# KEY_PLC1.net
KiCad netlist of a schematic drawn in Altium Designer
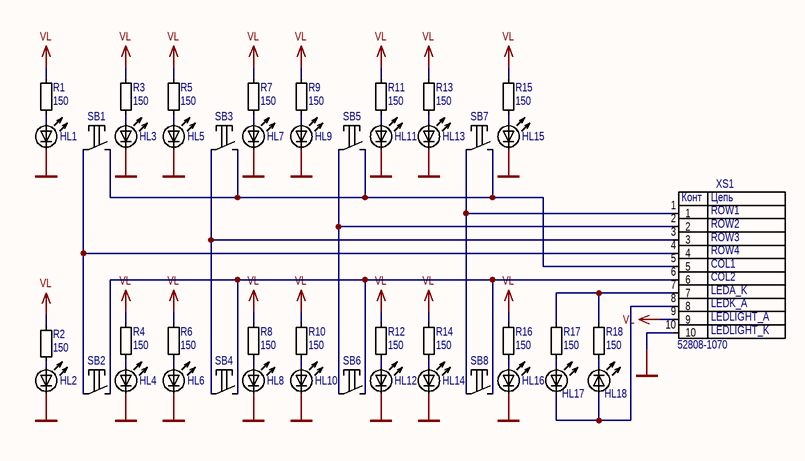
[diagram p0: KEY_PLC1.SchDoc]

(export (version "E")
  (design (tool "Eeschema 10.0.6"))
  (components
    (comp (ref "HL1")
      (value "BL-LS0805UYC")
      (footprint "LED_0805")
      (libsource (lib "KEY_PLC1") (part "BL-LS0805UYC"))
    )
    (comp (ref "HL2")
      (value "BL-LS0805UYC")
      (footprint "LED_0805")
      (libsource (lib "KEY_PLC1") (part "BL-LS0805UYC"))
    )
    (comp (ref "HL3")
      (value "BL-LS0805UYC")
      (footprint "LED_0805")
      (libsource (lib "KEY_PLC1") (part "BL-LS0805UYC"))
    )
    (comp (ref "HL4")
      (value "BL-LS0805UYC")
      (footprint "LED_0805")
      (libsource (lib "KEY_PLC1") (part "BL-LS0805UYC"))
    )
    (comp (ref "HL5")
      (value "BL-LS0805UYC")
      (footprint "LED_0805")
      (libsource (lib "KEY_PLC1") (part "BL-LS0805UYC"))
    )
    (comp (ref "HL6")
      (value "BL-LS0805UYC")
      (footprint "LED_0805")
      (libsource (lib "KEY_PLC1") (part "BL-LS0805UYC"))
    )
    (comp (ref "HL7")
      (value "BL-LS0805UYC")
      (footprint "LED_0805")
      (libsource (lib "KEY_PLC1") (part "BL-LS0805UYC"))
    )
    (comp (ref "HL8")
      (value "BL-LS0805UYC")
      (footprint "LED_0805")
      (libsource (lib "KEY_PLC1") (part "BL-LS0805UYC"))
    )
    (comp (ref "HL9")
      (value "BL-LS0805UYC")
      (footprint "LED_0805")
      (libsource (lib "KEY_PLC1") (part "BL-LS0805UYC"))
    )
    (comp (ref "HL10")
      (value "BL-LS0805UYC")
      (footprint "LED_0805")
      (libsource (lib "KEY_PLC1") (part "BL-LS0805UYC"))
    )
    (comp (ref "HL11")
      (value "BL-LS0805UYC")
      (footprint "LED_0805")
      (libsource (lib "KEY_PLC1") (part "BL-LS0805UYC"))
    )
    (comp (ref "HL12")
      (value "BL-LS0805UYC")
      (footprint "LED_0805")
      (libsource (lib "KEY_PLC1") (part "BL-LS0805UYC"))
    )
    (comp (ref "HL13")
      (value "BL-LS0805UYC")
      (footprint "LED_0805")
      (libsource (lib "KEY_PLC1") (part "BL-LS0805UYC"))
    )
    (comp (ref "HL14")
      (value "BL-LS0805UYC")
      (footprint "LED_0805")
      (libsource (lib "KEY_PLC1") (part "BL-LS0805UYC"))
    )
    (comp (ref "HL15")
      (value "BL-LS0805UYC")
      (footprint "LED_0805")
      (libsource (lib "KEY_PLC1") (part "BL-LS0805UYC"))
    )
    (comp (ref "HL16")
      (value "BL-LS0805UYC")
      (footprint "LED_0805")
      (libsource (lib "KEY_PLC1") (part "BL-LS0805UYC"))
    )
    (comp (ref "HL17")
      (value "BL-LS0805PGC")
      (footprint "LED_0805G")
      (libsource (lib "KEY_PLC1") (part "BL-LS0805PGC"))
    )
    (comp (ref "HL18")
      (value "BL-LS0805UHR")
      (footprint "LED_0805R")
      (fields (field (name "MANUFACTURER") "Betlux"))
      (libsource (lib "KEY_PLC1") (part "BL-LS0805UHR"))
    )
    (comp (ref "R1")
      (value "150")
      (footprint "RES_0603")
      (description "0603, 150")
      (fields (field (name "MANUFACTURER") "YAGEO") (field (name "PART NUMBER") "RC0603FR-07150RL"))
      (libsource (lib "PLC1") (part "Res_0603"))
    )
    (comp (ref "R2")
      (value "150")
      (footprint "RES_0603")
      (description "0603, 150")
      (fields (field (name "MANUFACTURER") "YAGEO") (field (name "PART NUMBER") "RC0603FR-07150RL"))
      (libsource (lib "PLC1") (part "Res_0603"))
    )
    (comp (ref "R3")
      (value "150")
      (footprint "RES_0603")
      (description "0603, 150")
      (fields (field (name "MANUFACTURER") "YAGEO") (field (name "PART NUMBER") "RC0603FR-07150RL"))
      (libsource (lib "PLC1") (part "Res_0603"))
    )
    (comp (ref "R4")
      (value "150")
      (footprint "RES_0603")
      (description "0603, 150")
      (fields (field (name "MANUFACTURER") "YAGEO") (field (name "PART NUMBER") "RC0603FR-07150RL"))
      (libsource (lib "PLC1") (part "Res_0603"))
    )
    (comp (ref "R5")
      (value "150")
      (footprint "RES_0603")
      (description "0603, 150")
      (fields (field (name "MANUFACTURER") "YAGEO") (field (name "PART NUMBER") "RC0603FR-07150RL"))
      (libsource (lib "PLC1") (part "Res_0603"))
    )
    (comp (ref "R6")
      (value "150")
      (footprint "RES_0603")
      (description "0603, 150")
      (fields (field (name "MANUFACTURER") "YAGEO") (field (name "PART NUMBER") "RC0603FR-07150RL"))
      (libsource (lib "PLC1") (part "Res_0603"))
    )
    (comp (ref "R7")
      (value "150")
      (footprint "RES_0603")
      (description "0603, 150")
      (fields (field (name "MANUFACTURER") "YAGEO") (field (name "PART NUMBER") "RC0603FR-07150RL"))
      (libsource (lib "PLC1") (part "Res_0603"))
    )
    (comp (ref "R8")
      (value "150")
      (footprint "RES_0603")
      (description "0603, 150")
      (fields (field (name "MANUFACTURER") "YAGEO") (field (name "PART NUMBER") "RC0603FR-07150RL"))
      (libsource (lib "PLC1") (part "Res_0603"))
    )
    (comp (ref "R9")
      (value "150")
      (footprint "RES_0603")
      (description "0603, 150")
      (fields (field (name "MANUFACTURER") "YAGEO") (field (name "PART NUMBER") "RC0603FR-07150RL"))
      (libsource (lib "PLC1") (part "Res_0603"))
    )
    (comp (ref "R10")
      (value "150")
      (footprint "RES_0603")
      (description "0603, 150")
      (fields (field (name "MANUFACTURER") "YAGEO") (field (name "PART NUMBER") "RC0603FR-07150RL"))
      (libsource (lib "PLC1") (part "Res_0603"))
    )
    (comp (ref "R11")
      (value "150")
      (footprint "RES_0603")
      (description "0603, 150")
      (fields (field (name "MANUFACTURER") "YAGEO") (field (name "PART NUMBER") "RC0603FR-07150RL"))
      (libsource (lib "PLC1") (part "Res_0603"))
    )
    (comp (ref "R12")
      (value "150")
      (footprint "RES_0603")
      (description "0603, 150")
      (fields (field (name "MANUFACTURER") "YAGEO") (field (name "PART NUMBER") "RC0603FR-07150RL"))
      (libsource (lib "PLC1") (part "Res_0603"))
    )
    (comp (ref "R13")
      (value "150")
      (footprint "RES_0603")
      (description "0603, 150")
      (fields (field (name "MANUFACTURER") "YAGEO") (field (name "PART NUMBER") "RC0603FR-07150RL"))
      (libsource (lib "PLC1") (part "Res_0603"))
    )
    (comp (ref "R14")
      (value "150")
      (footprint "RES_0603")
      (description "0603, 150")
      (fields (field (name "MANUFACTURER") "YAGEO") (field (name "PART NUMBER") "RC0603FR-07150RL"))
      (libsource (lib "PLC1") (part "Res_0603"))
    )
    (comp (ref "R15")
      (value "150")
      (footprint "RES_0603")
      (description "0603, 150")
      (fields (field (name "MANUFACTURER") "YAGEO") (field (name "PART NUMBER") "RC0603FR-07150RL"))
      (libsource (lib "PLC1") (part "Res_0603"))
    )
    (comp (ref "R16")
      (value "150")
      (footprint "RES_0603")
      (description "0603, 150")
      (fields (field (name "MANUFACTURER") "YAGEO") (field (name "PART NUMBER") "RC0603FR-07150RL"))
      (libsource (lib "PLC1") (part "Res_0603"))
    )
    (comp (ref "R17")
      (value "150")
      (footprint "RES_0603")
      (description "0603, 150")
      (fields (field (name "MANUFACTURER") "YAGEO") (field (name "PART NUMBER") "RC0603FR-07150RL"))
      (libsource (lib "PLC1") (part "Res_0603"))
    )
    (comp (ref "R18")
      (value "150")
      (footprint "RES_0603")
      (description "0603, 150")
      (fields (field (name "MANUFACTURER") "YAGEO") (field (name "PART NUMBER") "RC0603FR-07150RL"))
      (libsource (lib "PLC1") (part "Res_0603"))
    )
    (comp (ref "SB1")
      (value "1181")
      (footprint "1181")
      (description "IT-1181-180G-G")
      (libsource (lib "KEY_PLC1") (part "1181"))
    )
    (comp (ref "SB2")
      (value "1181")
      (footprint "1181")
      (description "IT-1181-180G-G")
      (libsource (lib "KEY_PLC1") (part "1181"))
    )
    (comp (ref "SB3")
      (value "1181")
      (footprint "1181")
      (description "IT-1181-180G-G")
      (libsource (lib "KEY_PLC1") (part "1181"))
    )
    (comp (ref "SB4")
      (value "1181")
      (footprint "1181")
      (description "IT-1181-180G-G")
      (libsource (lib "KEY_PLC1") (part "1181"))
    )
    (comp (ref "SB5")
      (value "1181")
      (footprint "1181")
      (description "IT-1181-180G-G")
      (libsource (lib "KEY_PLC1") (part "1181"))
    )
    (comp (ref "SB6")
      (value "1181")
      (footprint "1181")
      (description "IT-1181-180G-G")
      (libsource (lib "KEY_PLC1") (part "1181"))
    )
    (comp (ref "SB7")
      (value "1181")
      (footprint "1181")
      (description "IT-1181-180G-G")
      (libsource (lib "KEY_PLC1") (part "1181"))
    )
    (comp (ref "SB8")
      (value "1181")
      (footprint "1181")
      (description "IT-1181-180G-G")
      (libsource (lib "KEY_PLC1") (part "1181"))
    )
    (comp (ref "XS1")
      (value "52808-1070")
      (footprint "52808-1070")
      (description "MOLEX 10-way connector")
      (fields (field (name "MANUFACTURER") "Molex"))
      (libsource (lib "KEY_PLC1") (part "52808-1070"))
    )
  )
  (nets
    (net (code "1") (name "GND") (class "Default")
      (node (ref "HL1") (pin "1") (pinfunction "1_1") (pintype "passive"))
      (node (ref "HL10") (pin "1") (pinfunction "1_1") (pintype "passive"))
      (node (ref "HL11") (pin "1") (pinfunction "1_1") (pintype "passive"))
      (node (ref "HL12") (pin "1") (pinfunction "1_1") (pintype "passive"))
      (node (ref "HL13") (pin "1") (pinfunction "1_1") (pintype "passive"))
      (node (ref "HL14") (pin "1") (pinfunction "1_1") (pintype "passive"))
      (node (ref "HL15") (pin "1") (pinfunction "1_1") (pintype "passive"))
      (node (ref "HL16") (pin "1") (pinfunction "1_1") (pintype "passive"))
      (node (ref "HL2") (pin "1") (pinfunction "1_1") (pintype "passive"))
      (node (ref "HL3") (pin "1") (pinfunction "1_1") (pintype "passive"))
      (node (ref "HL4") (pin "1") (pinfunction "1_1") (pintype "passive"))
      (node (ref "HL5") (pin "1") (pinfunction "1_1") (pintype "passive"))
      (node (ref "HL6") (pin "1") (pinfunction "1_1") (pintype "passive"))
      (node (ref "HL7") (pin "1") (pinfunction "1_1") (pintype "passive"))
      (node (ref "HL8") (pin "1") (pinfunction "1_1") (pintype "passive"))
      (node (ref "HL9") (pin "1") (pinfunction "1_1") (pintype "passive"))
      (node (ref "XS1") (pin "10") (pinfunction "10_10") (pintype "passive"))
    )
    (net (code "2") (name "Net-(HL1-Pad2)") (class "Default")
      (node (ref "HL1") (pin "2") (pinfunction "2_2") (pintype "passive"))
      (node (ref "R1") (pin "1") (pinfunction "1_1") (pintype "passive"))
    )
    (net (code "3") (name "Net-(HL2-Pad2)") (class "Default")
      (node (ref "HL2") (pin "2") (pinfunction "2_2") (pintype "passive"))
      (node (ref "R2") (pin "1") (pinfunction "1_1") (pintype "passive"))
    )
    (net (code "4") (name "Net-(HL3-Pad2)") (class "Default")
      (node (ref "HL3") (pin "2") (pinfunction "2_2") (pintype "passive"))
      (node (ref "R3") (pin "1") (pinfunction "1_1") (pintype "passive"))
    )
    (net (code "5") (name "Net-(HL4-Pad2)") (class "Default")
      (node (ref "HL4") (pin "2") (pinfunction "2_2") (pintype "passive"))
      (node (ref "R4") (pin "1") (pinfunction "1_1") (pintype "passive"))
    )
    (net (code "6") (name "Net-(HL5-Pad2)") (class "Default")
      (node (ref "HL5") (pin "2") (pinfunction "2_2") (pintype "passive"))
      (node (ref "R5") (pin "1") (pinfunction "1_1") (pintype "passive"))
    )
    (net (code "7") (name "Net-(HL6-Pad2)") (class "Default")
      (node (ref "HL6") (pin "2") (pinfunction "2_2") (pintype "passive"))
      (node (ref "R6") (pin "1") (pinfunction "1_1") (pintype "passive"))
    )
    (net (code "8") (name "Net-(HL7-Pad2)") (class "Default")
      (node (ref "HL7") (pin "2") (pinfunction "2_2") (pintype "passive"))
      (node (ref "R7") (pin "1") (pinfunction "1_1") (pintype "passive"))
    )
    (net (code "9") (name "Net-(HL8-Pad2)") (class "Default")
      (node (ref "HL8") (pin "2") (pinfunction "2_2") (pintype "passive"))
      (node (ref "R8") (pin "1") (pinfunction "1_1") (pintype "passive"))
    )
    (net (code "10") (name "Net-(HL9-Pad2)") (class "Default")
      (node (ref "HL9") (pin "2") (pinfunction "2_2") (pintype "passive"))
      (node (ref "R9") (pin "1") (pinfunction "1_1") (pintype "passive"))
    )
    (net (code "11") (name "Net-(HL10-Pad2)") (class "Default")
      (node (ref "HL10") (pin "2") (pinfunction "2_2") (pintype "passive"))
      (node (ref "R10") (pin "1") (pinfunction "1_1") (pintype "passive"))
    )
    (net (code "12") (name "Net-(HL11-Pad2)") (class "Default")
      (node (ref "HL11") (pin "2") (pinfunction "2_2") (pintype "passive"))
      (node (ref "R11") (pin "1") (pinfunction "1_1") (pintype "passive"))
    )
    (net (code "13") (name "Net-(HL12-Pad2)") (class "Default")
      (node (ref "HL12") (pin "2") (pinfunction "2_2") (pintype "passive"))
      (node (ref "R12") (pin "1") (pinfunction "1_1") (pintype "passive"))
    )
    (net (code "14") (name "Net-(HL13-Pad2)") (class "Default")
      (node (ref "HL13") (pin "2") (pinfunction "2_2") (pintype "passive"))
      (node (ref "R13") (pin "1") (pinfunction "1_1") (pintype "passive"))
    )
    (net (code "15") (name "Net-(HL14-Pad2)") (class "Default")
      (node (ref "HL14") (pin "2") (pinfunction "2_2") (pintype "passive"))
      (node (ref "R14") (pin "1") (pinfunction "1_1") (pintype "passive"))
    )
    (net (code "16") (name "Net-(HL15-Pad2)") (class "Default")
      (node (ref "HL15") (pin "2") (pinfunction "2_2") (pintype "passive"))
      (node (ref "R15") (pin "1") (pinfunction "1_1") (pintype "passive"))
    )
    (net (code "17") (name "Net-(HL16-Pad2)") (class "Default")
      (node (ref "HL16") (pin "2") (pinfunction "2_2") (pintype "passive"))
      (node (ref "R16") (pin "1") (pinfunction "1_1") (pintype "passive"))
    )
    (net (code "18") (name "Net-(HL17-Pad1)") (class "Default")
      (node (ref "HL17") (pin "1") (pinfunction "1_1") (pintype "passive"))
      (node (ref "HL18") (pin "2") (pinfunction "2_2") (pintype "passive"))
      (node (ref "XS1") (pin "8") (pinfunction "8_8") (pintype "passive"))
    )
    (net (code "19") (name "Net-(HL17-Pad2)") (class "Default")
      (node (ref "HL17") (pin "2") (pinfunction "2_2") (pintype "passive"))
      (node (ref "R17") (pin "1") (pinfunction "1_1") (pintype "passive"))
    )
    (net (code "20") (name "Net-(HL18-Pad1)") (class "Default")
      (node (ref "HL18") (pin "1") (pinfunction "1_1") (pintype "passive"))
      (node (ref "R18") (pin "1") (pinfunction "1_1") (pintype "passive"))
    )
    (net (code "21") (name "Net-(R17-Pad2)") (class "Default")
      (node (ref "R17") (pin "2") (pinfunction "2_2") (pintype "passive"))
      (node (ref "R18") (pin "2") (pinfunction "2_2") (pintype "passive"))
      (node (ref "XS1") (pin "7") (pinfunction "7_7") (pintype "passive"))
    )
    (net (code "22") (name "Net-(SB1-Pad1)") (class "Default")
      (node (ref "SB1") (pin "1") (pintype "passive"))
      (node (ref "SB2") (pin "1") (pintype "passive"))
      (node (ref "XS1") (pin "4") (pinfunction "4_4") (pintype "passive"))
    )
    (net (code "23") (name "Net-(SB1-Pad2)") (class "Default")
      (node (ref "SB1") (pin "2") (pintype "passive"))
      (node (ref "SB3") (pin "2") (pintype "passive"))
      (node (ref "SB5") (pin "2") (pintype "passive"))
      (node (ref "SB7") (pin "2") (pintype "passive"))
      (node (ref "XS1") (pin "5") (pinfunction "5_5") (pintype "passive"))
    )
    (net (code "24") (name "Net-(SB2-Pad2)") (class "Default")
      (node (ref "SB2") (pin "2") (pintype "passive"))
      (node (ref "SB4") (pin "2") (pintype "passive"))
      (node (ref "SB6") (pin "2") (pintype "passive"))
      (node (ref "SB8") (pin "2") (pintype "passive"))
      (node (ref "XS1") (pin "6") (pinfunction "6_6") (pintype "passive"))
    )
    (net (code "25") (name "Net-(SB3-Pad1)") (class "Default")
      (node (ref "SB3") (pin "1") (pintype "passive"))
      (node (ref "SB4") (pin "1") (pintype "passive"))
      (node (ref "XS1") (pin "3") (pinfunction "3_3") (pintype "passive"))
    )
    (net (code "26") (name "Net-(SB5-Pad1)") (class "Default")
      (node (ref "SB5") (pin "1") (pintype "passive"))
      (node (ref "SB6") (pin "1") (pintype "passive"))
      (node (ref "XS1") (pin "2") (pinfunction "2_2") (pintype "passive"))
    )
    (net (code "27") (name "Net-(SB7-Pad1)") (class "Default")
      (node (ref "SB7") (pin "1") (pintype "passive"))
      (node (ref "SB8") (pin "1") (pintype "passive"))
      (node (ref "XS1") (pin "1") (pinfunction "1_1") (pintype "passive"))
    )
    (net (code "28") (name "VL") (class "Default")
      (node (ref "R1") (pin "2") (pinfunction "2_2") (pintype "passive"))
      (node (ref "R10") (pin "2") (pinfunction "2_2") (pintype "passive"))
      (node (ref "R11") (pin "2") (pinfunction "2_2") (pintype "passive"))
      (node (ref "R12") (pin "2") (pinfunction "2_2") (pintype "passive"))
      (node (ref "R13") (pin "2") (pinfunction "2_2") (pintype "passive"))
      (node (ref "R14") (pin "2") (pinfunction "2_2") (pintype "passive"))
      (node (ref "R15") (pin "2") (pinfunction "2_2") (pintype "passive"))
      (node (ref "R16") (pin "2") (pinfunction "2_2") (pintype "passive"))
      (node (ref "R2") (pin "2") (pinfunction "2_2") (pintype "passive"))
      (node (ref "R3") (pin "2") (pinfunction "2_2") (pintype "passive"))
      (node (ref "R4") (pin "2") (pinfunction "2_2") (pintype "passive"))
      (node (ref "R5") (pin "2") (pinfunction "2_2") (pintype "passive"))
      (node (ref "R6") (pin "2") (pinfunction "2_2") (pintype "passive"))
      (node (ref "R7") (pin "2") (pinfunction "2_2") (pintype "passive"))
      (node (ref "R8") (pin "2") (pinfunction "2_2") (pintype "passive"))
      (node (ref "R9") (pin "2") (pinfunction "2_2") (pintype "passive"))
      (node (ref "XS1") (pin "9") (pinfunction "9_9") (pintype "passive"))
    )
  )
)
